# comcon_version_thruhole.net
KiCad netlist of a schematic drawn in EAGLE
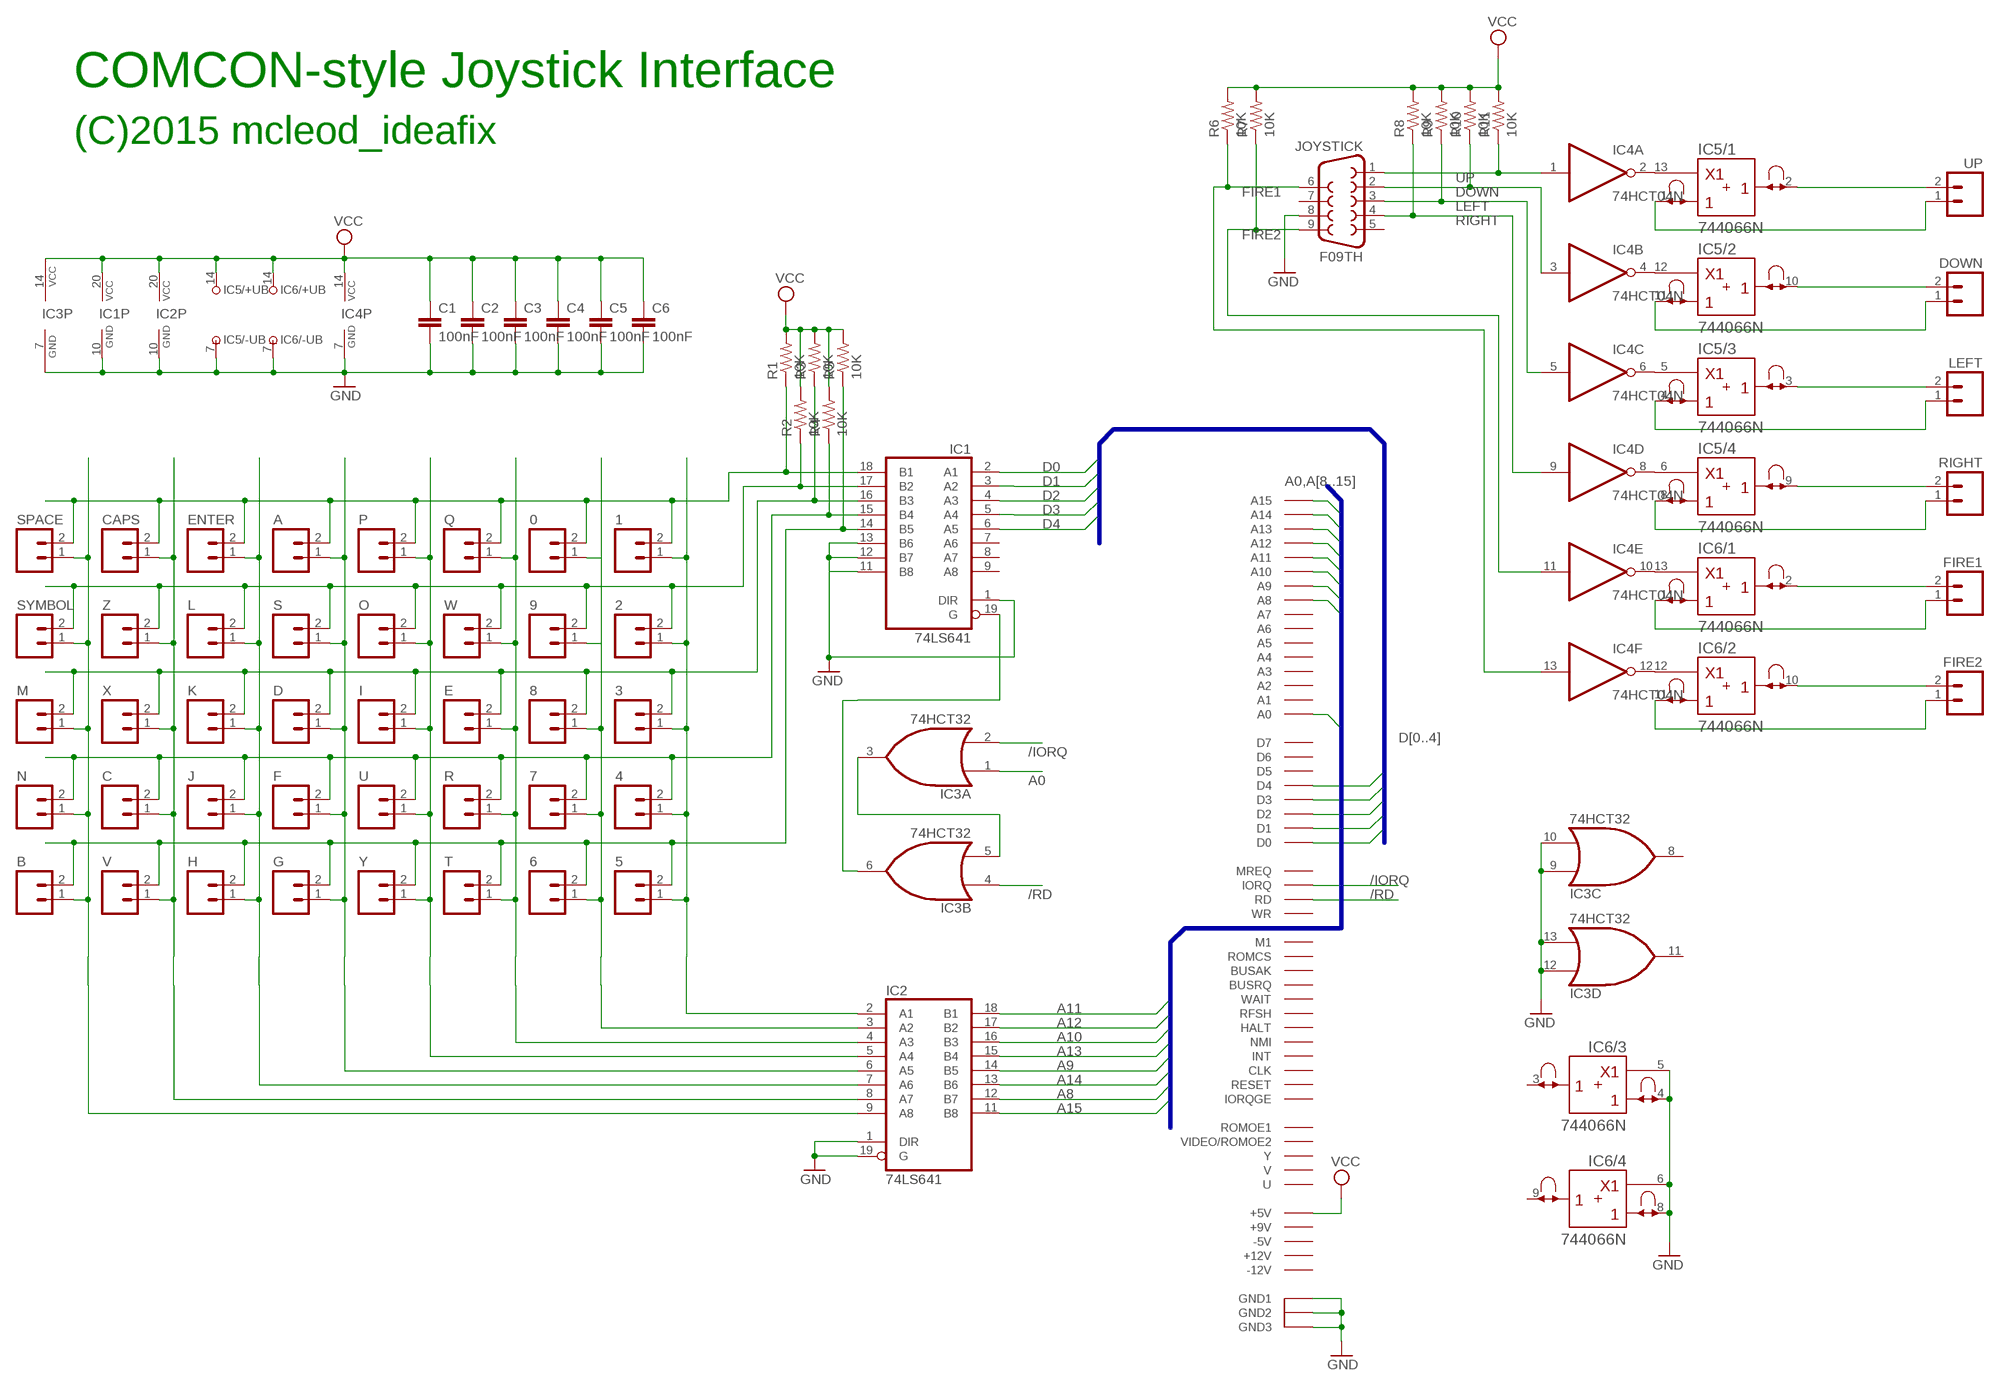
[diagram p0: schematic, sheet 1]

(export (version "E")
  (design (tool "Eeschema 10.0.6"))
  (components
    (comp (ref "0")
      (value "M02PTH")
      (footprint "eagle-import:1X02")
      (libsource (lib "eagle-import") (part "M02PTH"))
    )
    (comp (ref "1")
      (value "M02PTH")
      (footprint "eagle-import:1X02")
      (libsource (lib "eagle-import") (part "M02PTH"))
    )
    (comp (ref "2")
      (value "M02PTH")
      (footprint "eagle-import:1X02")
      (libsource (lib "eagle-import") (part "M02PTH"))
    )
    (comp (ref "3")
      (value "M02PTH")
      (footprint "eagle-import:1X02")
      (libsource (lib "eagle-import") (part "M02PTH"))
    )
    (comp (ref "4")
      (value "M02PTH")
      (footprint "eagle-import:1X02")
      (libsource (lib "eagle-import") (part "M02PTH"))
    )
    (comp (ref "5")
      (value "M02PTH")
      (footprint "eagle-import:1X02")
      (libsource (lib "eagle-import") (part "M02PTH"))
    )
    (comp (ref "6")
      (value "M02PTH")
      (footprint "eagle-import:1X02")
      (libsource (lib "eagle-import") (part "M02PTH"))
    )
    (comp (ref "7")
      (value "M02PTH")
      (footprint "eagle-import:1X02")
      (libsource (lib "eagle-import") (part "M02PTH"))
    )
    (comp (ref "8")
      (value "M02PTH")
      (footprint "eagle-import:1X02")
      (libsource (lib "eagle-import") (part "M02PTH"))
    )
    (comp (ref "9")
      (value "M02PTH")
      (footprint "eagle-import:1X02")
      (libsource (lib "eagle-import") (part "M02PTH"))
    )
    (comp (ref "A")
      (value "M02PTH")
      (footprint "eagle-import:1X02")
      (libsource (lib "eagle-import") (part "M02PTH"))
    )
    (comp (ref "B")
      (value "M02PTH")
      (footprint "eagle-import:1X02")
      (libsource (lib "eagle-import") (part "M02PTH"))
    )
    (comp (ref "C")
      (value "M02PTH")
      (footprint "eagle-import:1X02")
      (libsource (lib "eagle-import") (part "M02PTH"))
    )
    (comp (ref "C1")
      (value "100nF")
      (footprint "eagle-import:C050-025X075")
      (libsource (lib "eagle-import") (part "C-EU050-025X075"))
    )
    (comp (ref "C2")
      (value "100nF")
      (footprint "eagle-import:C050-025X075")
      (libsource (lib "eagle-import") (part "C-EU050-025X075"))
    )
    (comp (ref "C3")
      (value "100nF")
      (footprint "eagle-import:C050-025X075")
      (libsource (lib "eagle-import") (part "C-EU050-025X075"))
    )
    (comp (ref "C4")
      (value "100nF")
      (footprint "eagle-import:C050-025X075")
      (libsource (lib "eagle-import") (part "C-EU050-025X075"))
    )
    (comp (ref "C5")
      (value "100nF")
      (footprint "eagle-import:C050-025X075")
      (libsource (lib "eagle-import") (part "C-EU050-025X075"))
    )
    (comp (ref "C6")
      (value "100nF")
      (footprint "eagle-import:C050-025X075")
      (libsource (lib "eagle-import") (part "C-EU050-025X075"))
    )
    (comp (ref "CAPS")
      (value "M02PTH")
      (footprint "eagle-import:1X02")
      (libsource (lib "eagle-import") (part "M02PTH"))
    )
    (comp (ref "D")
      (value "M02PTH")
      (footprint "eagle-import:1X02")
      (libsource (lib "eagle-import") (part "M02PTH"))
    )
    (comp (ref "DOWN")
      (value "M02PTH")
      (footprint "eagle-import:1X02")
      (libsource (lib "eagle-import") (part "M02PTH"))
    )
    (comp (ref "E")
      (value "M02PTH")
      (footprint "eagle-import:1X02")
      (libsource (lib "eagle-import") (part "M02PTH"))
    )
    (comp (ref "ENTER")
      (value "M02PTH")
      (footprint "eagle-import:1X02")
      (libsource (lib "eagle-import") (part "M02PTH"))
    )
    (comp (ref "F")
      (value "M02PTH")
      (footprint "eagle-import:1X02")
      (libsource (lib "eagle-import") (part "M02PTH"))
    )
    (comp (ref "FIRE1")
      (value "M02PTH")
      (footprint "eagle-import:1X02")
      (libsource (lib "eagle-import") (part "M02PTH"))
    )
    (comp (ref "FIRE2")
      (value "M02PTH")
      (footprint "eagle-import:1X02")
      (libsource (lib "eagle-import") (part "M02PTH"))
    )
    (comp (ref "G")
      (value "M02PTH")
      (footprint "eagle-import:1X02")
      (libsource (lib "eagle-import") (part "M02PTH"))
    )
    (comp (ref "H")
      (value "M02PTH")
      (footprint "eagle-import:1X02")
      (libsource (lib "eagle-import") (part "M02PTH"))
    )
    (comp (ref "I")
      (value "M02PTH")
      (footprint "eagle-import:1X02")
      (libsource (lib "eagle-import") (part "M02PTH"))
    )
    (comp (ref "IC1")
      (value "74LS641")
      (footprint "eagle-import:DIL20")
      (libsource (lib "eagle-import") (part "74245NHCT"))
    )
    (comp (ref "IC2")
      (value "74LS641")
      (footprint "eagle-import:DIL20")
      (libsource (lib "eagle-import") (part "74245NHCT"))
    )
    (comp (ref "IC3")
      (value "74HCT32")
      (footprint "eagle-import:DIL14")
      (libsource (lib "eagle-import") (part "7432NLS"))
    )
    (comp (ref "IC4")
      (value "74HCT04N")
      (footprint "eagle-import:DIL14")
      (libsource (lib "eagle-import") (part "7404NHCT"))
    )
    (comp (ref "IC5")
      (value "744066N")
      (footprint "eagle-import:DIL14")
      (libsource (lib "eagle-import") (part "744066N"))
    )
    (comp (ref "IC6")
      (value "744066N")
      (footprint "eagle-import:DIL14")
      (libsource (lib "eagle-import") (part "744066N"))
    )
    (comp (ref "J")
      (value "M02PTH")
      (footprint "eagle-import:1X02")
      (libsource (lib "eagle-import") (part "M02PTH"))
    )
    (comp (ref "JOYSTICK")
      (value "F09TH")
      (footprint "eagle-import:DB9_PCB")
      (libsource (lib "eagle-import") (part "F09TH"))
    )
    (comp (ref "K")
      (value "M02PTH")
      (footprint "eagle-import:1X02")
      (libsource (lib "eagle-import") (part "M02PTH"))
    )
    (comp (ref "L")
      (value "M02PTH")
      (footprint "eagle-import:1X02")
      (libsource (lib "eagle-import") (part "M02PTH"))
    )
    (comp (ref "LEFT")
      (value "M02PTH")
      (footprint "eagle-import:1X02")
      (libsource (lib "eagle-import") (part "M02PTH"))
    )
    (comp (ref "M")
      (value "M02PTH")
      (footprint "eagle-import:1X02")
      (libsource (lib "eagle-import") (part "M02PTH"))
    )
    (comp (ref "N")
      (value "M02PTH")
      (footprint "eagle-import:1X02")
      (libsource (lib "eagle-import") (part "M02PTH"))
    )
    (comp (ref "O")
      (value "M02PTH")
      (footprint "eagle-import:1X02")
      (libsource (lib "eagle-import") (part "M02PTH"))
    )
    (comp (ref "P")
      (value "M02PTH")
      (footprint "eagle-import:1X02")
      (libsource (lib "eagle-import") (part "M02PTH"))
    )
    (comp (ref "Q")
      (value "M02PTH")
      (footprint "eagle-import:1X02")
      (libsource (lib "eagle-import") (part "M02PTH"))
    )
    (comp (ref "R")
      (value "M02PTH")
      (footprint "eagle-import:1X02")
      (libsource (lib "eagle-import") (part "M02PTH"))
    )
    (comp (ref "R1")
      (value "10K")
      (footprint "eagle-import:0207_10")
      (libsource (lib "eagle-import") (part "R-US_0207/10"))
    )
    (comp (ref "R2")
      (value "10K")
      (footprint "eagle-import:0207_10")
      (libsource (lib "eagle-import") (part "R-US_0207/10"))
    )
    (comp (ref "R3")
      (value "10K")
      (footprint "eagle-import:0207_10")
      (libsource (lib "eagle-import") (part "R-US_0207/10"))
    )
    (comp (ref "R4")
      (value "10K")
      (footprint "eagle-import:0207_10")
      (libsource (lib "eagle-import") (part "R-US_0207/10"))
    )
    (comp (ref "R5")
      (value "10K")
      (footprint "eagle-import:0207_10")
      (libsource (lib "eagle-import") (part "R-US_0207/10"))
    )
    (comp (ref "R6")
      (value "10K")
      (footprint "eagle-import:0207_10")
      (libsource (lib "eagle-import") (part "R-US_0207/10"))
    )
    (comp (ref "R7")
      (value "10K")
      (footprint "eagle-import:0207_10")
      (libsource (lib "eagle-import") (part "R-US_0207/10"))
    )
    (comp (ref "R8")
      (value "10K")
      (footprint "eagle-import:0207_10")
      (libsource (lib "eagle-import") (part "R-US_0207/10"))
    )
    (comp (ref "R9")
      (value "10K")
      (footprint "eagle-import:0207_10")
      (libsource (lib "eagle-import") (part "R-US_0207/10"))
    )
    (comp (ref "R10")
      (value "10K")
      (footprint "eagle-import:0207_10")
      (libsource (lib "eagle-import") (part "R-US_0207/10"))
    )
    (comp (ref "R11")
      (value "10K")
      (footprint "eagle-import:0207_10")
      (libsource (lib "eagle-import") (part "R-US_0207/10"))
    )
    (comp (ref "RIGHT")
      (value "M02PTH")
      (footprint "eagle-import:1X02")
      (libsource (lib "eagle-import") (part "M02PTH"))
    )
    (comp (ref "S")
      (value "M02PTH")
      (footprint "eagle-import:1X02")
      (libsource (lib "eagle-import") (part "M02PTH"))
    )
    (comp (ref "SPACE")
      (value "M02PTH")
      (footprint "eagle-import:1X02")
      (libsource (lib "eagle-import") (part "M02PTH"))
    )
    (comp (ref "SYMBOL")
      (value "M02PTH")
      (footprint "eagle-import:1X02")
      (libsource (lib "eagle-import") (part "M02PTH"))
    )
    (comp (ref "T")
      (value "M02PTH")
      (footprint "eagle-import:1X02")
      (libsource (lib "eagle-import") (part "M02PTH"))
    )
    (comp (ref "U")
      (value "M02PTH")
      (footprint "eagle-import:1X02")
      (libsource (lib "eagle-import") (part "M02PTH"))
    )
    (comp (ref "UP")
      (value "M02PTH")
      (footprint "eagle-import:1X02")
      (libsource (lib "eagle-import") (part "M02PTH"))
    )
    (comp (ref "V")
      (value "M02PTH")
      (footprint "eagle-import:1X02")
      (libsource (lib "eagle-import") (part "M02PTH"))
    )
    (comp (ref "W")
      (value "M02PTH")
      (footprint "eagle-import:1X02")
      (libsource (lib "eagle-import") (part "M02PTH"))
    )
    (comp (ref "X")
      (value "M02PTH")
      (footprint "eagle-import:1X02")
      (libsource (lib "eagle-import") (part "M02PTH"))
    )
    (comp (ref "Y")
      (value "M02PTH")
      (footprint "eagle-import:1X02")
      (libsource (lib "eagle-import") (part "M02PTH"))
    )
    (comp (ref "Z")
      (value "M02PTH")
      (footprint "eagle-import:1X02")
      (libsource (lib "eagle-import") (part "M02PTH"))
    )
    (comp (ref "ZX_BUS")
      (value "CONECTOR_SPECTRUM")
      (footprint "eagle-import:CONECTOR_SPECTRUM")
      (libsource (lib "eagle-import") (part "CONECTOR_SPECTRUM"))
    )
  )
  (nets
    (net (code "9") (name "/A0") (class "Default")
      (node (ref "IC3") (pin "1") (pinfunction "I0_1") (pintype "input"))
      (node (ref "ZX_BUS") (pin "A0") (pinfunction "A0_A0") (pintype "bidirectional"))
    )
    (net (code "11") (name "/A8") (class "Default")
      (node (ref "IC2") (pin "12") (pinfunction "B7_12") (pintype "bidirectional"))
      (node (ref "ZX_BUS") (pin "A8") (pinfunction "A8_A8") (pintype "bidirectional"))
    )
    (net (code "12") (name "/A9") (class "Default")
      (node (ref "IC2") (pin "14") (pinfunction "B5_14") (pintype "bidirectional"))
      (node (ref "ZX_BUS") (pin "A9") (pinfunction "A9_A9") (pintype "bidirectional"))
    )
    (net (code "13") (name "/A10") (class "Default")
      (node (ref "IC2") (pin "16") (pinfunction "B3_16") (pintype "bidirectional"))
      (node (ref "ZX_BUS") (pin "A10") (pinfunction "A10_A10") (pintype "bidirectional"))
    )
    (net (code "14") (name "/A11") (class "Default")
      (node (ref "IC2") (pin "18") (pinfunction "B1_18") (pintype "bidirectional"))
      (node (ref "ZX_BUS") (pin "A11") (pinfunction "A11_A11") (pintype "bidirectional"))
    )
    (net (code "15") (name "/A12") (class "Default")
      (node (ref "IC2") (pin "17") (pinfunction "B2_17") (pintype "bidirectional"))
      (node (ref "ZX_BUS") (pin "A12") (pinfunction "A12_A12") (pintype "bidirectional"))
    )
    (net (code "16") (name "/A13") (class "Default")
      (node (ref "IC2") (pin "15") (pinfunction "B4_15") (pintype "bidirectional"))
      (node (ref "ZX_BUS") (pin "A13") (pinfunction "A13_A13") (pintype "bidirectional"))
    )
    (net (code "17") (name "/A14") (class "Default")
      (node (ref "IC2") (pin "13") (pinfunction "B6_13") (pintype "bidirectional"))
      (node (ref "ZX_BUS") (pin "A14") (pinfunction "A14_A14") (pintype "bidirectional"))
    )
    (net (code "18") (name "/A15") (class "Default")
      (node (ref "IC2") (pin "11") (pinfunction "B8_11") (pintype "bidirectional"))
      (node (ref "ZX_BUS") (pin "A15") (pinfunction "A15_A15") (pintype "bidirectional"))
    )
    (net (code "19") (name "/D0") (class "Default")
      (node (ref "IC1") (pin "2") (pinfunction "A1_2") (pintype "bidirectional"))
      (node (ref "ZX_BUS") (pin "D0") (pinfunction "D0_D0") (pintype "bidirectional"))
    )
    (net (code "20") (name "/D1") (class "Default")
      (node (ref "IC1") (pin "3") (pinfunction "A2_3") (pintype "bidirectional"))
      (node (ref "ZX_BUS") (pin "D1") (pinfunction "D1_D1") (pintype "bidirectional"))
    )
    (net (code "21") (name "/D2") (class "Default")
      (node (ref "IC1") (pin "4") (pinfunction "A3_4") (pintype "bidirectional"))
      (node (ref "ZX_BUS") (pin "D2") (pinfunction "D2_D2") (pintype "bidirectional"))
    )
    (net (code "22") (name "/D3") (class "Default")
      (node (ref "IC1") (pin "5") (pinfunction "A4_5") (pintype "bidirectional"))
      (node (ref "ZX_BUS") (pin "D3") (pinfunction "D3_D3") (pintype "bidirectional"))
    )
    (net (code "23") (name "/D4") (class "Default")
      (node (ref "IC1") (pin "6") (pinfunction "A5_6") (pintype "bidirectional"))
      (node (ref "ZX_BUS") (pin "D4") (pinfunction "D4_D4") (pintype "bidirectional"))
    )
    (net (code "24") (name "/DOWN") (class "Default")
      (node (ref "IC4") (pin "3") (pinfunction "I_3") (pintype "input"))
      (node (ref "JOYSTICK") (pin "2") (pinfunction "2_2") (pintype "passive"))
      (node (ref "R10") (pin "1") (pinfunction "1_1") (pintype "passive"))
    )
    (net (code "26") (name "/FIRE1") (class "Default")
      (node (ref "IC4") (pin "13") (pinfunction "I_13") (pintype "input"))
      (node (ref "JOYSTICK") (pin "6") (pinfunction "6_6") (pintype "passive"))
      (node (ref "R6") (pin "1") (pinfunction "1_1") (pintype "passive"))
    )
    (net (code "27") (name "/FIRE2") (class "Default")
      (node (ref "IC4") (pin "11") (pinfunction "I_11") (pintype "input"))
      (node (ref "JOYSTICK") (pin "9") (pinfunction "9_9") (pintype "passive"))
      (node (ref "R7") (pin "1") (pinfunction "1_1") (pintype "passive"))
    )
    (net (code "28") (name "/LEFT") (class "Default")
      (node (ref "IC4") (pin "5") (pinfunction "I_5") (pintype "input"))
      (node (ref "JOYSTICK") (pin "3") (pinfunction "3_3") (pintype "passive"))
      (node (ref "R9") (pin "1") (pinfunction "1_1") (pintype "passive"))
    )
    (net (code "29") (name "/RIGHT") (class "Default")
      (node (ref "IC4") (pin "9") (pinfunction "I_9") (pintype "input"))
      (node (ref "JOYSTICK") (pin "4") (pinfunction "4_4") (pintype "passive"))
      (node (ref "R8") (pin "1") (pinfunction "1_1") (pintype "passive"))
    )
    (net (code "30") (name "/UP") (class "Default")
      (node (ref "IC4") (pin "1") (pinfunction "I_1") (pintype "input"))
      (node (ref "JOYSTICK") (pin "1") (pinfunction "1_1") (pintype "passive"))
      (node (ref "R11") (pin "1") (pinfunction "1_1") (pintype "passive"))
    )
    (net (code "31") (name "/{slash}IORQ") (class "Default")
      (node (ref "IC3") (pin "2") (pinfunction "I1_2") (pintype "input"))
      (node (ref "ZX_BUS") (pin "IORQ") (pinfunction "IORQ_IORQ") (pintype "bidirectional"))
    )
    (net (code "32") (name "/{slash}RD") (class "Default")
      (node (ref "IC3") (pin "4") (pinfunction "I0_4") (pintype "input"))
      (node (ref "ZX_BUS") (pin "RD") (pinfunction "RD_RD") (pintype "bidirectional"))
    )
    (net (code "33") (name "GND") (class "Default")
      (node (ref "C1") (pin "2") (pinfunction "2_2") (pintype "passive"))
      (node (ref "C2") (pin "2") (pinfunction "2_2") (pintype "passive"))
      (node (ref "C3") (pin "2") (pinfunction "2_2") (pintype "passive"))
      (node (ref "C4") (pin "2") (pinfunction "2_2") (pintype "passive"))
      (node (ref "C5") (pin "2") (pinfunction "2_2") (pintype "passive"))
      (node (ref "C6") (pin "2") (pinfunction "2_2") (pintype "passive"))
      (node (ref "IC1") (pin "1") (pinfunction "DIR_1") (pintype "input"))
      (node (ref "IC1") (pin "10") (pinfunction "GND_10") (pintype "power_in"))
      (node (ref "IC1") (pin "11") (pinfunction "B8_11") (pintype "bidirectional"))
      (node (ref "IC1") (pin "12") (pinfunction "B7_12") (pintype "bidirectional"))
      (node (ref "IC1") (pin "13") (pinfunction "B6_13") (pintype "bidirectional"))
      (node (ref "IC2") (pin "1") (pinfunction "DIR_1") (pintype "input"))
      (node (ref "IC2") (pin "10") (pinfunction "GND_10") (pintype "power_in"))
      (node (ref "IC2") (pin "19") (pinfunction "G_19") (pintype "input"))
      (node (ref "IC3") (pin "10") (pinfunction "I1_10") (pintype "input"))
      (node (ref "IC3") (pin "12") (pinfunction "I0_12") (pintype "input"))
      (node (ref "IC3") (pin "13") (pinfunction "I1_13") (pintype "input"))
      (node (ref "IC3") (pin "7") (pinfunction "GND_7") (pintype "power_in"))
      (node (ref "IC3") (pin "9") (pinfunction "I0_9") (pintype "input"))
      (node (ref "IC4") (pin "7") (pinfunction "GND_7") (pintype "power_in"))
      (node (ref "IC5") (pin "7") (pinfunction "-UB_7") (pintype "power_in"))
      (node (ref "IC6") (pin "4") (pinfunction "A_4") (pintype "passive"))
      (node (ref "IC6") (pin "5") (pinfunction "C_5") (pintype "input"))
      (node (ref "IC6") (pin "6") (pinfunction "C_6") (pintype "input"))
      (node (ref "IC6") (pin "7") (pinfunction "-UB_7") (pintype "power_in"))
      (node (ref "IC6") (pin "8") (pinfunction "A_8") (pintype "passive"))
      (node (ref "JOYSTICK") (pin "8") (pinfunction "8_8") (pintype "passive"))
      (node (ref "ZX_BUS") (pin "GND1") (pinfunction "GND1_GND1") (pintype "bidirectional"))
      (node (ref "ZX_BUS") (pin "GND2") (pinfunction "GND2_GND2") (pintype "bidirectional"))
      (node (ref "ZX_BUS") (pin "GND3") (pinfunction "GND3_GND3") (pintype "bidirectional"))
    )
    (net (code "34") (name "Net-(IC1A-B1)") (class "Default")
      (node (ref "0") (pin "2") (pinfunction "2_2") (pintype "passive"))
      (node (ref "1") (pin "2") (pinfunction "2_2") (pintype "passive"))
      (node (ref "A") (pin "2") (pinfunction "2_2") (pintype "passive"))
      (node (ref "CAPS") (pin "2") (pinfunction "2_2") (pintype "passive"))
      (node (ref "ENTER") (pin "2") (pinfunction "2_2") (pintype "passive"))
      (node (ref "IC1") (pin "18") (pinfunction "B1_18") (pintype "bidirectional"))
      (node (ref "P") (pin "2") (pinfunction "2_2") (pintype "passive"))
      (node (ref "Q") (pin "2") (pinfunction "2_2") (pintype "passive"))
      (node (ref "R1") (pin "1") (pinfunction "1_1") (pintype "passive"))
      (node (ref "SPACE") (pin "2") (pinfunction "2_2") (pintype "passive"))
    )
    (net (code "35") (name "Net-(IC1A-B2)") (class "Default")
      (node (ref "2") (pin "2") (pinfunction "2_2") (pintype "passive"))
      (node (ref "9") (pin "2") (pinfunction "2_2") (pintype "passive"))
      (node (ref "IC1") (pin "17") (pinfunction "B2_17") (pintype "bidirectional"))
      (node (ref "L") (pin "2") (pinfunction "2_2") (pintype "passive"))
      (node (ref "O") (pin "2") (pinfunction "2_2") (pintype "passive"))
      (node (ref "R2") (pin "1") (pinfunction "1_1") (pintype "passive"))
      (node (ref "S") (pin "2") (pinfunction "2_2") (pintype "passive"))
      (node (ref "SYMBOL") (pin "2") (pinfunction "2_2") (pintype "passive"))
      (node (ref "W") (pin "2") (pinfunction "2_2") (pintype "passive"))
      (node (ref "Z") (pin "2") (pinfunction "2_2") (pintype "passive"))
    )
    (net (code "36") (name "Net-(IC1A-B3)") (class "Default")
      (node (ref "3") (pin "2") (pinfunction "2_2") (pintype "passive"))
      (node (ref "8") (pin "2") (pinfunction "2_2") (pintype "passive"))
      (node (ref "D") (pin "2") (pinfunction "2_2") (pintype "passive"))
      (node (ref "E") (pin "2") (pinfunction "2_2") (pintype "passive"))
      (node (ref "I") (pin "2") (pinfunction "2_2") (pintype "passive"))
      (node (ref "IC1") (pin "16") (pinfunction "B3_16") (pintype "bidirectional"))
      (node (ref "K") (pin "2") (pinfunction "2_2") (pintype "passive"))
      (node (ref "M") (pin "2") (pinfunction "2_2") (pintype "passive"))
      (node (ref "R3") (pin "1") (pinfunction "1_1") (pintype "passive"))
      (node (ref "X") (pin "2") (pinfunction "2_2") (pintype "passive"))
    )
    (net (code "37") (name "Net-(IC1A-B4)") (class "Default")
      (node (ref "4") (pin "2") (pinfunction "2_2") (pintype "passive"))
      (node (ref "7") (pin "2") (pinfunction "2_2") (pintype "passive"))
      (node (ref "C") (pin "2") (pinfunction "2_2") (pintype "passive"))
      (node (ref "F") (pin "2") (pinfunction "2_2") (pintype "passive"))
      (node (ref "IC1") (pin "15") (pinfunction "B4_15") (pintype "bidirectional"))
      (node (ref "J") (pin "2") (pinfunction "2_2") (pintype "passive"))
      (node (ref "N") (pin "2") (pinfunction "2_2") (pintype "passive"))
      (node (ref "R") (pin "2") (pinfunction "2_2") (pintype "passive"))
      (node (ref "R4") (pin "1") (pinfunction "1_1") (pintype "passive"))
      (node (ref "U") (pin "2") (pinfunction "2_2") (pintype "passive"))
    )
    (net (code "38") (name "Net-(IC1A-B5)") (class "Default")
      (node (ref "5") (pin "2") (pinfunction "2_2") (pintype "passive"))
      (node (ref "6") (pin "2") (pinfunction "2_2") (pintype "passive"))
      (node (ref "B") (pin "2") (pinfunction "2_2") (pintype "passive"))
      (node (ref "G") (pin "2") (pinfunction "2_2") (pintype "passive"))
      (node (ref "H") (pin "2") (pinfunction "2_2") (pintype "passive"))
      (node (ref "IC1") (pin "14") (pinfunction "B5_14") (pintype "bidirectional"))
      (node (ref "R5") (pin "1") (pinfunction "1_1") (pintype "passive"))
      (node (ref "T") (pin "2") (pinfunction "2_2") (pintype "passive"))
      (node (ref "V") (pin "2") (pinfunction "2_2") (pintype "passive"))
      (node (ref "Y") (pin "2") (pinfunction "2_2") (pintype "passive"))
    )
    (net (code "39") (name "Net-(IC1A-G)") (class "Default")
      (node (ref "IC1") (pin "19") (pinfunction "G_19") (pintype "input"))
      (node (ref "IC3") (pin "6") (pinfunction "O_6") (pintype "output"))
    )
    (net (code "40") (name "Net-(IC2A-A1)") (class "Default")
      (node (ref "1") (pin "1") (pinfunction "1_1") (pintype "passive"))
      (node (ref "2") (pin "1") (pinfunction "1_1") (pintype "passive"))
      (node (ref "3") (pin "1") (pinfunction "1_1") (pintype "passive"))
      (node (ref "4") (pin "1") (pinfunction "1_1") (pintype "passive"))
      (node (ref "5") (pin "1") (pinfunction "1_1") (pintype "passive"))
      (node (ref "IC2") (pin "2") (pinfunction "A1_2") (pintype "bidirectional"))
    )
    (net (code "41") (name "Net-(IC2A-A2)") (class "Default")
      (node (ref "0") (pin "1") (pinfunction "1_1") (pintype "passive"))
      (node (ref "6") (pin "1") (pinfunction "1_1") (pintype "passive"))
      (node (ref "7") (pin "1") (pinfunction "1_1") (pintype "passive"))
      (node (ref "8") (pin "1") (pinfunction "1_1") (pintype "passive"))
      (node (ref "9") (pin "1") (pinfunction "1_1") (pintype "passive"))
      (node (ref "IC2") (pin "3") (pinfunction "A2_3") (pintype "bidirectional"))
    )
    (net (code "42") (name "Net-(IC2A-A3)") (class "Default")
      (node (ref "E") (pin "1") (pinfunction "1_1") (pintype "passive"))
      (node (ref "IC2") (pin "4") (pinfunction "A3_4") (pintype "bidirectional"))
      (node (ref "Q") (pin "1") (pinfunction "1_1") (pintype "passive"))
      (node (ref "R") (pin "1") (pinfunction "1_1") (pintype "passive"))
      (node (ref "T") (pin "1") (pinfunction "1_1") (pintype "passive"))
      (node (ref "W") (pin "1") (pinfunction "1_1") (pintype "passive"))
    )
    (net (code "43") (name "Net-(IC2A-A4)") (class "Default")
      (node (ref "I") (pin "1") (pinfunction "1_1") (pintype "passive"))
      (node (ref "IC2") (pin "5") (pinfunction "A4_5") (pintype "bidirectional"))
      (node (ref "O") (pin "1") (pinfunction "1_1") (pintype "passive"))
      (node (ref "P") (pin "1") (pinfunction "1_1") (pintype "passive"))
      (node (ref "U") (pin "1") (pinfunction "1_1") (pintype "passive"))
      (node (ref "Y") (pin "1") (pinfunction "1_1") (pintype "passive"))
    )
    (net (code "44") (name "Net-(IC2A-A5)") (class "Default")
      (node (ref "A") (pin "1") (pinfunction "1_1") (pintype "passive"))
      (node (ref "D") (pin "1") (pinfunction "1_1") (pintype "passive"))
      (node (ref "F") (pin "1") (pinfunction "1_1") (pintype "passive"))
      (node (ref "G") (pin "1") (pinfunction "1_1") (pintype "passive"))
      (node (ref "IC2") (pin "6") (pinfunction "A5_6") (pintype "bidirectional"))
      (node (ref "S") (pin "1") (pinfunction "1_1") (pintype "passive"))
    )
    (net (code "45") (name "Net-(IC2A-A6)") (class "Default")
      (node (ref "ENTER") (pin "1") (pinfunction "1_1") (pintype "passive"))
      (node (ref "H") (pin "1") (pinfunction "1_1") (pintype "passive"))
      (node (ref "IC2") (pin "7") (pinfunction "A6_7") (pintype "bidirectional"))
      (node (ref "J") (pin "1") (pinfunction "1_1") (pintype "passive"))
      (node (ref "K") (pin "1") (pinfunction "1_1") (pintype "passive"))
      (node (ref "L") (pin "1") (pinfunction "1_1") (pintype "passive"))
    )
    (net (code "46") (name "Net-(IC2A-A7)") (class "Default")
      (node (ref "C") (pin "1") (pinfunction "1_1") (pintype "passive"))
      (node (ref "CAPS") (pin "1") (pinfunction "1_1") (pintype "passive"))
      (node (ref "IC2") (pin "8") (pinfunction "A7_8") (pintype "bidirectional"))
      (node (ref "V") (pin "1") (pinfunction "1_1") (pintype "passive"))
      (node (ref "X") (pin "1") (pinfunction "1_1") (pintype "passive"))
      (node (ref "Z") (pin "1") (pinfunction "1_1") (pintype "passive"))
    )
    (net (code "47") (name "Net-(IC2A-A8)") (class "Default")
      (node (ref "B") (pin "1") (pinfunction "1_1") (pintype "passive"))
      (node (ref "IC2") (pin "9") (pinfunction "A8_9") (pintype "bidirectional"))
      (node (ref "M") (pin "1") (pinfunction "1_1") (pintype "passive"))
      (node (ref "N") (pin "1") (pinfunction "1_1") (pintype "passive"))
      (node (ref "SPACE") (pin "1") (pinfunction "1_1") (pintype "passive"))
      (node (ref "SYMBOL") (pin "1") (pinfunction "1_1") (pintype "passive"))
    )
    (net (code "48") (name "Net-(IC3A-O)") (class "Default")
      (node (ref "IC3") (pin "3") (pinfunction "O_3") (pintype "output"))
      (node (ref "IC3") (pin "5") (pinfunction "I1_5") (pintype "input"))
    )
    (net (code "49") (name "Net-(IC4A-O)") (class "Default")
      (node (ref "IC4") (pin "2") (pinfunction "O_2") (pintype "output"))
      (node (ref "IC5") (pin "13") (pinfunction "C_13") (pintype "input"))
    )
    (net (code "50") (name "Net-(IC4B-O)") (class "Default")
      (node (ref "IC4") (pin "4") (pinfunction "O_4") (pintype "output"))
      (node (ref "IC5") (pin "12") (pinfunction "C_12") (pintype "input"))
    )
    (net (code "51") (name "Net-(IC4C-O)") (class "Default")
      (node (ref "IC4") (pin "6") (pinfunction "O_6") (pintype "output"))
      (node (ref "IC5") (pin "5") (pinfunction "C_5") (pintype "input"))
    )
    (net (code "52") (name "Net-(IC4D-O)") (class "Default")
      (node (ref "IC4") (pin "8") (pinfunction "O_8") (pintype "output"))
      (node (ref "IC5") (pin "6") (pinfunction "C_6") (pintype "input"))
    )
    (net (code "53") (name "Net-(IC4E-O)") (class "Default")
      (node (ref "IC4") (pin "10") (pinfunction "O_10") (pintype "output"))
      (node (ref "IC6") (pin "13") (pinfunction "C_13") (pintype "input"))
    )
    (net (code "54") (name "Net-(IC4F-O)") (class "Default")
      (node (ref "IC4") (pin "12") (pinfunction "O_12") (pintype "output"))
      (node (ref "IC6") (pin "12") (pinfunction "C_12") (pintype "input"))
    )
    (net (code "55") (name "Net-(IC5C-A)") (class "Default")
      (node (ref "IC5") (pin "1") (pinfunction "A_1") (pintype "passive"))
      (node (ref "UP") (pin "1") (pinfunction "1_1") (pintype "passive"))
    )
    (net (code "56") (name "Net-(IC5C-B)") (class "Default")
      (node (ref "IC5") (pin "2") (pinfunction "B_2") (pintype "passive"))
      (node (ref "UP") (pin "2") (pinfunction "2_2") (pintype "passive"))
    )
    (net (code "57") (name "Net-(IC5D-A)") (class "Default")
      (node (ref "DOWN") (pin "1") (pinfunction "1_1") (pintype "passive"))
      (node (ref "IC5") (pin "11") (pinfunction "A_11") (pintype "passive"))
    )
    (net (code "58") (name "Net-(IC5D-B)") (class "Default")
      (node (ref "DOWN") (pin "2") (pinfunction "2_2") (pintype "passive"))
      (node (ref "IC5") (pin "10") (pinfunction "B_10") (pintype "passive"))
    )
    (net (code "59") (name "Net-(IC5E-A)") (class "Default")
      (node (ref "IC5") (pin "4") (pinfunction "A_4") (pintype "passive"))
      (node (ref "LEFT") (pin "1") (pinfunction "1_1") (pintype "passive"))
    )
    (net (code "60") (name "Net-(IC5E-B)") (class "Default")
      (node (ref "IC5") (pin "3") (pinfunction "B_3") (pintype "passive"))
      (node (ref "LEFT") (pin "2") (pinfunction "2_2") (pintype "passive"))
    )
    (net (code "61") (name "Net-(IC5F-A)") (class "Default")
      (node (ref "IC5") (pin "8") (pinfunction "A_8") (pintype "passive"))
      (node (ref "RIGHT") (pin "1") (pinfunction "1_1") (pintype "passive"))
    )
    (net (code "62") (name "Net-(IC5F-B)") (class "Default")
      (node (ref "IC5") (pin "9") (pinfunction "B_9") (pintype "passive"))
      (node (ref "RIGHT") (pin "2") (pinfunction "2_2") (pintype "passive"))
    )
    (net (code "63") (name "Net-(IC6C-A)") (class "Default")
      (node (ref "FIRE1") (pin "1") (pinfunction "1_1") (pintype "passive"))
      (node (ref "IC6") (pin "1") (pinfunction "A_1") (pintype "passive"))
    )
    (net (code "64") (name "Net-(IC6C-B)") (class "Default")
      (node (ref "FIRE1") (pin "2") (pinfunction "2_2") (pintype "passive"))
      (node (ref "IC6") (pin "2") (pinfunction "B_2") (pintype "passive"))
    )
    (net (code "65") (name "Net-(IC6D-A)") (class "Default")
      (node (ref "FIRE2") (pin "1") (pinfunction "1_1") (pintype "passive"))
      (node (ref "IC6") (pin "11") (pinfunction "A_11") (pintype "passive"))
    )
    (net (code "66") (name "Net-(IC6D-B)") (class "Default")
      (node (ref "FIRE2") (pin "2") (pinfunction "2_2") (pintype "passive"))
      (node (ref "IC6") (pin "10") (pinfunction "B_10") (pintype "passive"))
    )
    (net (code "67") (name "VCC") (class "Default")
      (node (ref "C1") (pin "1") (pinfunction "1_1") (pintype "passive"))
      (node (ref "C2") (pin "1") (pinfunction "1_1") (pintype "passive"))
      (node (ref "C3") (pin "1") (pinfunction "1_1") (pintype "passive"))
      (node (ref "C4") (pin "1") (pinfunction "1_1") (pintype "passive"))
      (node (ref "C5") (pin "1") (pinfunction "1_1") (pintype "passive"))
      (node (ref "C6") (pin "1") (pinfunction "1_1") (pintype "passive"))
      (node (ref "IC1") (pin "20") (pinfunction "VCC_20") (pintype "power_in"))
      (node (ref "IC2") (pin "20") (pinfunction "VCC_20") (pintype "power_in"))
      (node (ref "IC3") (pin "14") (pinfunction "VCC_14") (pintype "power_in"))
      (node (ref "IC4") (pin "14") (pinfunction "VCC_14") (pintype "power_in"))
      (node (ref "IC5") (pin "14") (pinfunction "+UB_14") (pintype "power_in"))
      (node (ref "IC6") (pin "14") (pinfunction "+UB_14") (pintype "power_in"))
      (node (ref "R1") (pin "2") (pinfunction "2_2") (pintype "passive"))
      (node (ref "R10") (pin "2") (pinfunction "2_2") (pintype "passive"))
      (node (ref "R11") (pin "2") (pinfunction "2_2") (pintype "passive"))
      (node (ref "R2") (pin "2") (pinfunction "2_2") (pintype "passive"))
      (node (ref "R3") (pin "2") (pinfunction "2_2") (pintype "passive"))
      (node (ref "R4") (pin "2") (pinfunction "2_2") (pintype "passive"))
      (node (ref "R5") (pin "2") (pinfunction "2_2") (pintype "passive"))
      (node (ref "R6") (pin "2") (pinfunction "2_2") (pintype "passive"))
      (node (ref "R7") (pin "2") (pinfunction "2_2") (pintype "passive"))
      (node (ref "R8") (pin "2") (pinfunction "2_2") (pintype "passive"))
      (node (ref "R9") (pin "2") (pinfunction "2_2") (pintype "passive"))
      (node (ref "ZX_BUS") (pin "+5V") (pinfunction "+5V_+5V") (pintype "bidirectional"))
    )
    (net (code "68") (name "unconnected-(IC1A-A6-Pad7)") (class "Default")
      (node (ref "IC1") (pin "7") (pinfunction "A6_7") (pintype "bidirectional"))
    )
    (net (code "69") (name "unconnected-(IC1A-A7-Pad8)") (class "Default")
      (node (ref "IC1") (pin "8") (pinfunction "A7_8") (pintype "bidirectional"))
    )
    (net (code "70") (name "unconnected-(IC1A-A8-Pad9)") (class "Default")
      (node (ref "IC1") (pin "9") (pinfunction "A8_9") (pintype "bidirectional"))
    )
    (net (code "71") (name "unconnected-(IC3C-O-Pad8)") (class "Default")
      (node (ref "IC3") (pin "8") (pinfunction "O_8") (pintype "output"))
    )
    (net (code "72") (name "unconnected-(IC3D-O-Pad11)") (class "Default")
      (node (ref "IC3") (pin "11") (pinfunction "O_11") (pintype "output"))
    )
    (net (code "73") (name "unconnected-(IC6E-B-Pad3)") (class "Default")
      (node (ref "IC6") (pin "3") (pinfunction "B_3") (pintype "passive"))
    )
    (net (code "74") (name "unconnected-(IC6F-B-Pad9)") (class "Default")
      (node (ref "IC6") (pin "9") (pinfunction "B_9") (pintype "passive"))
    )
    (net (code "75") (name "unconnected-(JOYSTICK-Pad5)") (class "Default")
      (node (ref "JOYSTICK") (pin "5") (pinfunction "5_5") (pintype "passive"))
    )
    (net (code "76") (name "unconnected-(JOYSTICK-Pad7)") (class "Default")
      (node (ref "JOYSTICK") (pin "7") (pinfunction "7_7") (pintype "passive"))
    )
    (net (code "77") (name "unconnected-(ZX_BUS-MREQ-PadMERQ)") (class "Default")
      (node (ref "ZX_BUS") (pin "MERQ") (pinfunction "MREQ_MERQ") (pintype "bidirectional"))
    )
    (net (code "78") (name "unconnected-(ZX_BUS-Pad+9V)") (class "Default")
      (node (ref "ZX_BUS") (pin "+9V") (pinfunction "+9V_+9V") (pintype "bidirectional"))
    )
    (net (code "79") (name "unconnected-(ZX_BUS-Pad+12V)") (class "Default")
      (node (ref "ZX_BUS") (pin "+12V") (pinfunction "+12V_+12V") (pintype "bidirectional"))
    )
    (net (code "80") (name "unconnected-(ZX_BUS-Pad-5V)") (class "Default")
      (node (ref "ZX_BUS") (pin "-5V") (pinfunction "-5V_-5V") (pintype "bidirectional"))
    )
    (net (code "81") (name "unconnected-(ZX_BUS-Pad-12V)") (class "Default")
      (node (ref "ZX_BUS") (pin "-12V") (pinfunction "-12V_-12V") (pintype "bidirectional"))
    )
    (net (code "82") (name "unconnected-(ZX_BUS-PadA1)") (class "Default")
      (node (ref "ZX_BUS") (pin "A1") (pinfunction "A1_A1") (pintype "bidirectional"))
    )
    (net (code "83") (name "unconnected-(ZX_BUS-PadA2)") (class "Default")
      (node (ref "ZX_BUS") (pin "A2") (pinfunction "A2_A2") (pintype "bidirectional"))
    )
    (net (code "84") (name "unconnected-(ZX_BUS-PadA3)") (class "Default")
      (node (ref "ZX_BUS") (pin "A3") (pinfunction "A3_A3") (pintype "bidirectional"))
    )
    (net (code "85") (name "unconnected-(ZX_BUS-PadA4)") (class "Default")
      (node (ref "ZX_BUS") (pin "A4") (pinfunction "A4_A4") (pintype "bidirectional"))
    )
    (net (code "86") (name "unconnected-(ZX_BUS-PadA5)") (class "Default")
      (node (ref "ZX_BUS") (pin "A5") (pinfunction "A5_A5") (pintype "bidirectional"))
    )
    (net (code "87") (name "unconnected-(ZX_BUS-PadA6)") (class "Default")
      (node (ref "ZX_BUS") (pin "A6") (pinfunction "A6_A6") (pintype "bidirectional"))
    )
    (net (code "88") (name "unconnected-(ZX_BUS-PadA7)") (class "Default")
      (node (ref "ZX_BUS") (pin "A7") (pinfunction "A7_A7") (pintype "bidirectional"))
    )
    (net (code "89") (name "unconnected-(ZX_BUS-PadBUSAK)") (class "Default")
      (node (ref "ZX_BUS") (pin "BUSAK") (pinfunction "BUSAK_BUSAK") (pintype "bidirectional"))
    )
    (net (code "90") (name "unconnected-(ZX_BUS-PadBUSRQ)") (class "Default")
      (node (ref "ZX_BUS") (pin "BUSRQ") (pinfunction "BUSRQ_BUSRQ") (pintype "bidirectional"))
    )
    (net (code "91") (name "unconnected-(ZX_BUS-PadCLK)") (class "Default")
      (node (ref "ZX_BUS") (pin "CLK") (pinfunction "CLK_CLK") (pintype "bidirectional"))
    )
    (net (code "92") (name "unconnected-(ZX_BUS-PadD5)") (class "Default")
      (node (ref "ZX_BUS") (pin "D5") (pinfunction "D5_D5") (pintype "bidirectional"))
    )
    (net (code "93") (name "unconnected-(ZX_BUS-PadD6)") (class "Default")
      (node (ref "ZX_BUS") (pin "D6") (pinfunction "D6_D6") (pintype "bidirectional"))
    )
    (net (code "94") (name "unconnected-(ZX_BUS-PadD7)") (class "Default")
      (node (ref "ZX_BUS") (pin "D7") (pinfunction "D7_D7") (pintype "bidirectional"))
    )
    (net (code "95") (name "unconnected-(ZX_BUS-PadHALT)") (class "Default")
      (node (ref "ZX_BUS") (pin "HALT") (pinfunction "HALT_HALT") (pintype "bidirectional"))
    )
    (net (code "96") (name "unconnected-(ZX_BUS-PadINT)") (class "Default")
      (node (ref "ZX_BUS") (pin "INT") (pinfunction "INT_INT") (pintype "bidirectional"))
    )
    (net (code "97") (name "unconnected-(ZX_BUS-PadIORQGE)") (class "Default")
      (node (ref "ZX_BUS") (pin "IORQGE") (pinfunction "IORQGE_IORQGE") (pintype "bidirectional"))
    )
    (net (code "98") (name "unconnected-(ZX_BUS-PadM1)") (class "Default")
      (node (ref "ZX_BUS") (pin "M1") (pinfunction "M1_M1") (pintype "bidirectional"))
    )
    (net (code "99") (name "unconnected-(ZX_BUS-PadNMI)") (class "Default")
      (node (ref "ZX_BUS") (pin "NMI") (pinfunction "NMI_NMI") (pintype "bidirectional"))
    )
    (net (code "100") (name "unconnected-(ZX_BUS-PadRESET)") (class "Default")
      (node (ref "ZX_BUS") (pin "RESET") (pinfunction "RESET_RESET") (pintype "bidirectional"))
    )
    (net (code "101") (name "unconnected-(ZX_BUS-PadRFSH)") (class "Default")
      (node (ref "ZX_BUS") (pin "RFSH") (pinfunction "RFSH_RFSH") (pintype "bidirectional"))
    )
    (net (code "102") (name "unconnected-(ZX_BUS-PadROMCS)") (class "Default")
      (node (ref "ZX_BUS") (pin "ROMCS") (pinfunction "ROMCS_ROMCS") (pintype "bidirectional"))
    )
    (net (code "103") (name "unconnected-(ZX_BUS-PadU)") (class "Default")
      (node (ref "ZX_BUS") (pin "U") (pinfunction "U_U") (pintype "bidirectional"))
    )
    (net (code "104") (name "unconnected-(ZX_BUS-PadV)") (class "Default")
      (node (ref "ZX_BUS") (pin "V") (pinfunction "V_V") (pintype "bidirectional"))
    )
    (net (code "105") (name "unconnected-(ZX_BUS-PadWAIT)") (class "Default")
      (node (ref "ZX_BUS") (pin "WAIT") (pinfunction "WAIT_WAIT") (pintype "bidirectional"))
    )
    (net (code "106") (name "unconnected-(ZX_BUS-PadWR)") (class "Default")
      (node (ref "ZX_BUS") (pin "WR") (pinfunction "WR_WR") (pintype "bidirectional"))
    )
    (net (code "107") (name "unconnected-(ZX_BUS-PadY)") (class "Default")
      (node (ref "ZX_BUS") (pin "Y") (pinfunction "Y_Y") (pintype "bidirectional"))
    )
    (net (code "108") (name "unconnected-(ZX_BUS-ROMOE1-PadNC1)") (class "Default")
      (node (ref "ZX_BUS") (pin "NC1") (pinfunction "ROMOE1_NC1") (pintype "bidirectional"))
    )
    (net (code "109") (name "unconnected-(ZX_BUS-VIDEO{slash}ROMOE2-PadVIDEO)") (class "Default")
      (node (ref "ZX_BUS") (pin "VIDEO") (pinfunction "VIDEO/ROMOE2_VIDEO") (pintype "bidirectional"))
    )
  )
)
